# Schematic.net
KiCad netlist of a schematic drawn in EAGLE
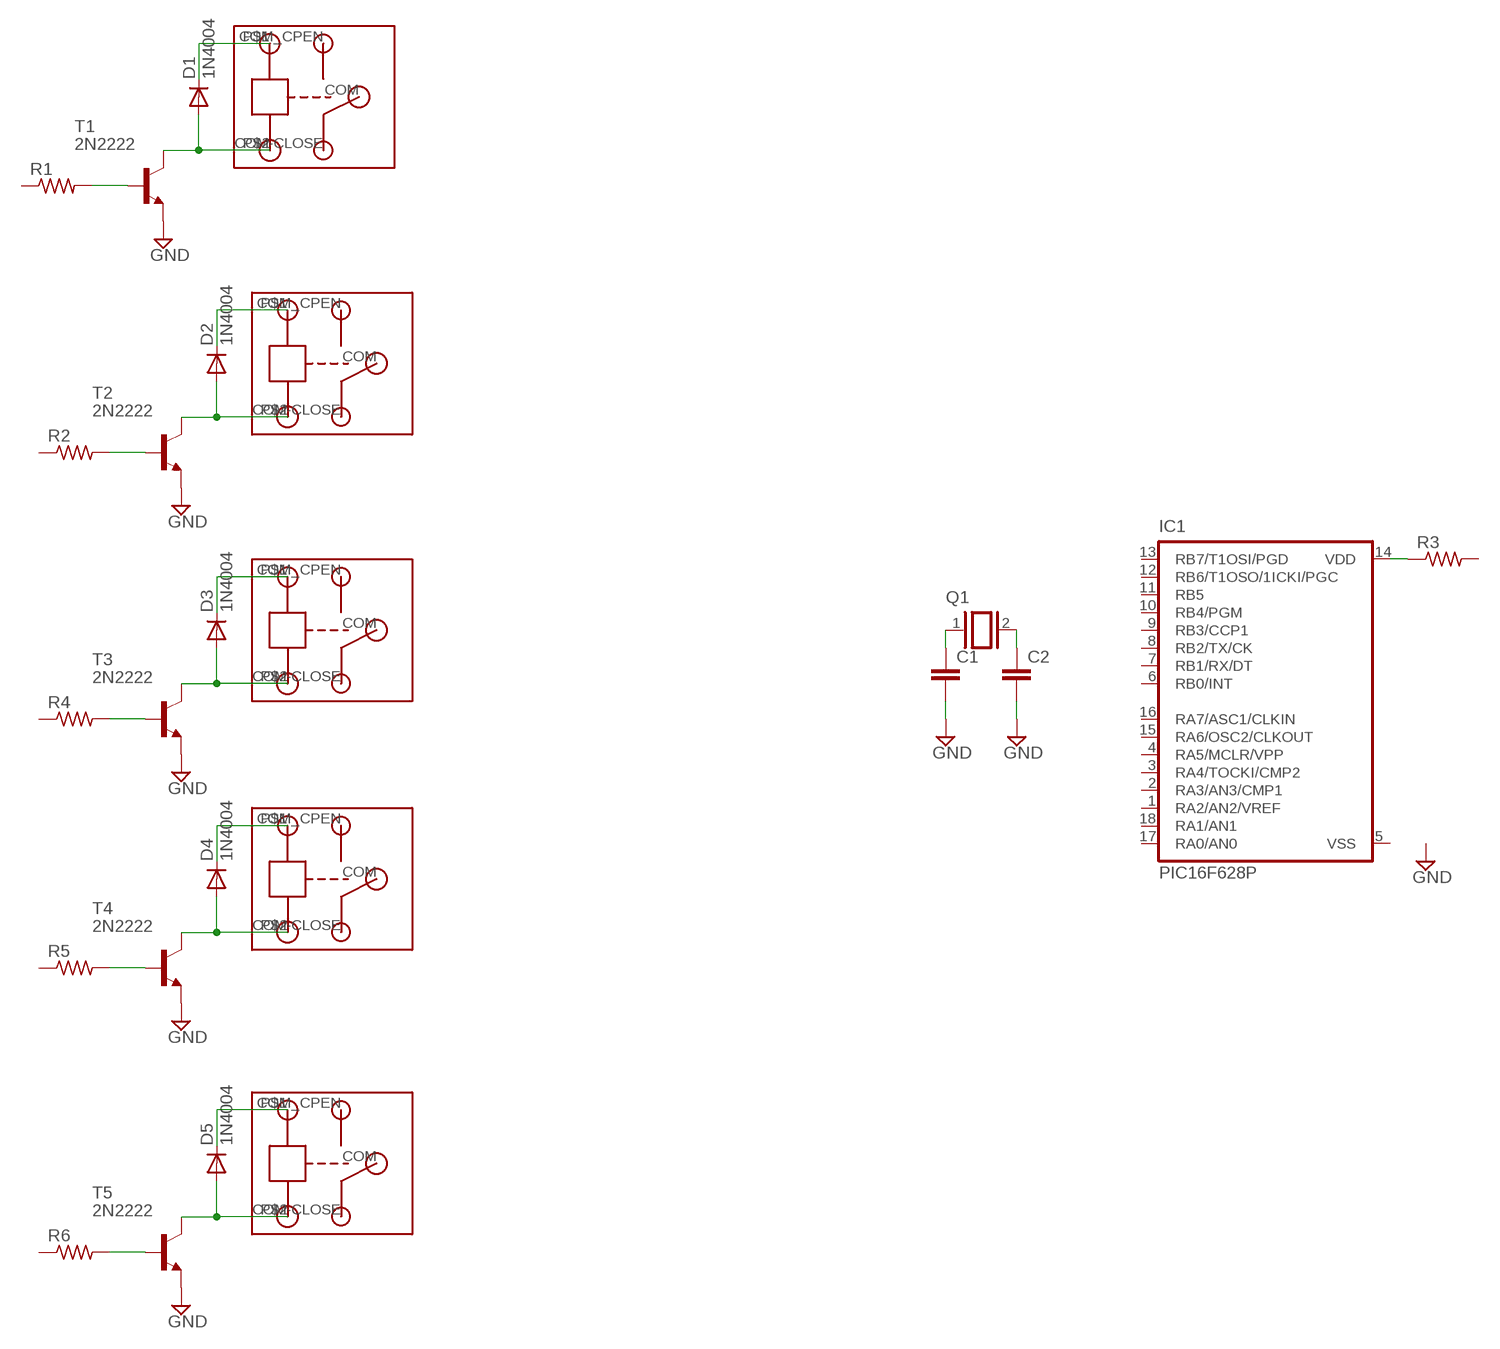
[diagram p0: schematic, sheet 1]

(export (version "E")
  (design (tool "Eeschema 10.0.6"))
  (components
    (comp (ref "C1")
      (value "C2,5-3")
      (footprint "eagle-import:C2.5-3")
      (libsource (lib "eagle-import") (part "C2,5-3"))
    )
    (comp (ref "C2")
      (value "C2,5-3")
      (footprint "eagle-import:C2.5-3")
      (libsource (lib "eagle-import") (part "C2,5-3"))
    )
    (comp (ref "D1")
      (value "1N4004")
      (footprint "eagle-import:DO41-10")
      (libsource (lib "eagle-import") (part "1N4004"))
    )
    (comp (ref "D2")
      (value "1N4004")
      (footprint "eagle-import:DO41-10")
      (libsource (lib "eagle-import") (part "1N4004"))
    )
    (comp (ref "D3")
      (value "1N4004")
      (footprint "eagle-import:DO41-10")
      (libsource (lib "eagle-import") (part "1N4004"))
    )
    (comp (ref "D4")
      (value "1N4004")
      (footprint "eagle-import:DO41-10")
      (libsource (lib "eagle-import") (part "1N4004"))
    )
    (comp (ref "D5")
      (value "1N4004")
      (footprint "eagle-import:DO41-10")
      (libsource (lib "eagle-import") (part "1N4004"))
    )
    (comp (ref "IC1")
      (value "PIC16F628P")
      (footprint "eagle-import:DIL18")
      (fields (field (name "MF") "MICROCHIP") (field (name "MPN") "PIC16F628-20/P"))
      (libsource (lib "eagle-import") (part "PIC16F628P"))
    )
    (comp (ref "Q1")
      (value "XTAL")
      (footprint "eagle-import:Q")
      (libsource (lib "eagle-import") (part "XTAL"))
    )
    (comp (ref "R1")
      (value "R-US_0207/7")
      (footprint "eagle-import:0207_7")
      (libsource (lib "eagle-import") (part "R-US_0207/7"))
    )
    (comp (ref "R2")
      (value "R-US_0207/7")
      (footprint "eagle-import:0207_7")
      (libsource (lib "eagle-import") (part "R-US_0207/7"))
    )
    (comp (ref "R3")
      (value "R-US_0207/12")
      (footprint "eagle-import:0207_12")
      (libsource (lib "eagle-import") (part "R-US_0207/12"))
    )
    (comp (ref "R4")
      (value "R-US_0207/7")
      (footprint "eagle-import:0207_7")
      (libsource (lib "eagle-import") (part "R-US_0207/7"))
    )
    (comp (ref "R5")
      (value "R-US_0207/7")
      (footprint "eagle-import:0207_7")
      (libsource (lib "eagle-import") (part "R-US_0207/7"))
    )
    (comp (ref "R6")
      (value "R-US_0207/7")
      (footprint "eagle-import:0207_7")
      (libsource (lib "eagle-import") (part "R-US_0207/7"))
    )
    (comp (ref "T1")
      (value "2N2222")
      (footprint "eagle-import:TO92-EBC-OVAL")
      (libsource (lib "eagle-import") (part "2N2222"))
    )
    (comp (ref "T2")
      (value "2N2222")
      (footprint "eagle-import:TO92-EBC-OVAL")
      (libsource (lib "eagle-import") (part "2N2222"))
    )
    (comp (ref "T3")
      (value "2N2222")
      (footprint "eagle-import:TO92-EBC-OVAL")
      (libsource (lib "eagle-import") (part "2N2222"))
    )
    (comp (ref "T4")
      (value "2N2222")
      (footprint "eagle-import:TO92-EBC-OVAL")
      (libsource (lib "eagle-import") (part "2N2222"))
    )
    (comp (ref "T5")
      (value "2N2222")
      (footprint "eagle-import:TO92-EBC-OVAL")
      (libsource (lib "eagle-import") (part "2N2222"))
    )
    (comp (ref "U$1")
      (value "RELAY")
      (footprint "eagle-import:RELAY")
      (libsource (lib "eagle-import") (part "RELAY"))
    )
    (comp (ref "U$2")
      (value "RELAY")
      (footprint "eagle-import:RELAY")
      (libsource (lib "eagle-import") (part "RELAY"))
    )
    (comp (ref "U$3")
      (value "RELAY")
      (footprint "eagle-import:RELAY")
      (libsource (lib "eagle-import") (part "RELAY"))
    )
    (comp (ref "U$4")
      (value "RELAY")
      (footprint "eagle-import:RELAY")
      (libsource (lib "eagle-import") (part "RELAY"))
    )
    (comp (ref "U$5")
      (value "RELAY")
      (footprint "eagle-import:RELAY")
      (libsource (lib "eagle-import") (part "RELAY"))
    )
  )
  (nets
    (net (code "1") (name "/VSS") (class "Default")
      (node (ref "IC1") (pin "5") (pinfunction "VSS_5") (pintype "power_in"))
    )
    (net (code "2") (name "GND") (class "Default")
      (node (ref "C1") (pin "2") (pinfunction "2_2") (pintype "passive"))
      (node (ref "C2") (pin "2") (pinfunction "2_2") (pintype "passive"))
      (node (ref "T1") (pin "E") (pinfunction "E_E") (pintype "passive"))
      (node (ref "T2") (pin "E") (pinfunction "E_E") (pintype "passive"))
      (node (ref "T3") (pin "E") (pinfunction "E_E") (pintype "passive"))
      (node (ref "T4") (pin "E") (pinfunction "E_E") (pintype "passive"))
      (node (ref "T5") (pin "E") (pinfunction "E_E") (pintype "passive"))
    )
    (net (code "3") (name "Net-(C1-Pad1)") (class "Default")
      (node (ref "C1") (pin "1") (pinfunction "1_1") (pintype "passive"))
      (node (ref "Q1") (pin "1") (pinfunction "1_1") (pintype "passive"))
    )
    (net (code "4") (name "Net-(C2-Pad1)") (class "Default")
      (node (ref "C2") (pin "1") (pinfunction "1_1") (pintype "passive"))
      (node (ref "Q1") (pin "2") (pinfunction "2_2") (pintype "passive"))
    )
    (net (code "5") (name "Net-(IC1-VDD)") (class "Default")
      (node (ref "IC1") (pin "14") (pinfunction "VDD_14") (pintype "power_in"))
      (node (ref "R3") (pin "1") (pinfunction "1_1") (pintype "passive"))
    )
    (net (code "6") (name "Net-(R1-Pad2)") (class "Default")
      (node (ref "R1") (pin "2") (pinfunction "2_2") (pintype "passive"))
      (node (ref "T1") (pin "B") (pinfunction "B_B") (pintype "passive"))
    )
    (net (code "7") (name "Net-(R2-Pad2)") (class "Default")
      (node (ref "R2") (pin "2") (pinfunction "2_2") (pintype "passive"))
      (node (ref "T2") (pin "B") (pinfunction "B_B") (pintype "passive"))
    )
    (net (code "8") (name "Net-(R4-Pad2)") (class "Default")
      (node (ref "R4") (pin "2") (pinfunction "2_2") (pintype "passive"))
      (node (ref "T3") (pin "B") (pinfunction "B_B") (pintype "passive"))
    )
    (net (code "9") (name "Net-(R5-Pad2)") (class "Default")
      (node (ref "R5") (pin "2") (pinfunction "2_2") (pintype "passive"))
      (node (ref "T4") (pin "B") (pinfunction "B_B") (pintype "passive"))
    )
    (net (code "10") (name "Net-(R6-Pad2)") (class "Default")
      (node (ref "R6") (pin "2") (pinfunction "2_2") (pintype "passive"))
      (node (ref "T5") (pin "B") (pinfunction "B_B") (pintype "passive"))
    )
    (net (code "11") (name "Net-(U$1-GND)") (class "Default")
      (node (ref "D1") (pin "A") (pinfunction "A_A") (pintype "passive"))
      (node (ref "T1") (pin "C") (pinfunction "C_C") (pintype "passive"))
      (node (ref "U$1") (pin "P$2") (pinfunction "GND_P$2") (pintype "bidirectional"))
    )
    (net (code "12") (name "Net-(U$1-IN)") (class "Default")
      (node (ref "D1") (pin "C") (pinfunction "C_C") (pintype "passive"))
      (node (ref "U$1") (pin "P$1") (pinfunction "IN_P$1") (pintype "bidirectional"))
    )
    (net (code "13") (name "Net-(U$2-GND)") (class "Default")
      (node (ref "D2") (pin "A") (pinfunction "A_A") (pintype "passive"))
      (node (ref "T2") (pin "C") (pinfunction "C_C") (pintype "passive"))
      (node (ref "U$2") (pin "P$2") (pinfunction "GND_P$2") (pintype "bidirectional"))
    )
    (net (code "14") (name "Net-(U$2-IN)") (class "Default")
      (node (ref "D2") (pin "C") (pinfunction "C_C") (pintype "passive"))
      (node (ref "U$2") (pin "P$1") (pinfunction "IN_P$1") (pintype "bidirectional"))
    )
    (net (code "15") (name "Net-(U$3-GND)") (class "Default")
      (node (ref "D3") (pin "A") (pinfunction "A_A") (pintype "passive"))
      (node (ref "T3") (pin "C") (pinfunction "C_C") (pintype "passive"))
      (node (ref "U$3") (pin "P$2") (pinfunction "GND_P$2") (pintype "bidirectional"))
    )
    (net (code "16") (name "Net-(U$3-IN)") (class "Default")
      (node (ref "D3") (pin "C") (pinfunction "C_C") (pintype "passive"))
      (node (ref "U$3") (pin "P$1") (pinfunction "IN_P$1") (pintype "bidirectional"))
    )
    (net (code "17") (name "Net-(U$4-GND)") (class "Default")
      (node (ref "D4") (pin "A") (pinfunction "A_A") (pintype "passive"))
      (node (ref "T4") (pin "C") (pinfunction "C_C") (pintype "passive"))
      (node (ref "U$4") (pin "P$2") (pinfunction "GND_P$2") (pintype "bidirectional"))
    )
    (net (code "18") (name "Net-(U$4-IN)") (class "Default")
      (node (ref "D4") (pin "C") (pinfunction "C_C") (pintype "passive"))
      (node (ref "U$4") (pin "P$1") (pinfunction "IN_P$1") (pintype "bidirectional"))
    )
    (net (code "19") (name "Net-(U$5-GND)") (class "Default")
      (node (ref "D5") (pin "A") (pinfunction "A_A") (pintype "passive"))
      (node (ref "T5") (pin "C") (pinfunction "C_C") (pintype "passive"))
      (node (ref "U$5") (pin "P$2") (pinfunction "GND_P$2") (pintype "bidirectional"))
    )
    (net (code "20") (name "Net-(U$5-IN)") (class "Default")
      (node (ref "D5") (pin "C") (pinfunction "C_C") (pintype "passive"))
      (node (ref "U$5") (pin "P$1") (pinfunction "IN_P$1") (pintype "bidirectional"))
    )
    (net (code "21") (name "unconnected-(IC1-RA0{slash}AN0-Pad17)") (class "Default")
      (node (ref "IC1") (pin "17") (pinfunction "RA0/AN0_17") (pintype "bidirectional"))
    )
    (net (code "22") (name "unconnected-(IC1-RA1{slash}AN1-Pad18)") (class "Default")
      (node (ref "IC1") (pin "18") (pinfunction "RA1/AN1_18") (pintype "bidirectional"))
    )
    (net (code "23") (name "unconnected-(IC1-RA2{slash}AN2{slash}VREF-Pad1)") (class "Default")
      (node (ref "IC1") (pin "1") (pinfunction "RA2/AN2/VREF_1") (pintype "bidirectional"))
    )
    (net (code "24") (name "unconnected-(IC1-RA3{slash}AN3{slash}CMP1-Pad2)") (class "Default")
      (node (ref "IC1") (pin "2") (pinfunction "RA3/AN3/CMP1_2") (pintype "bidirectional"))
    )
    (net (code "25") (name "unconnected-(IC1-RA4{slash}TOCKI{slash}CMP2-Pad3)") (class "Default")
      (node (ref "IC1") (pin "3") (pinfunction "RA4/TOCKI/CMP2_3") (pintype "bidirectional"))
    )
    (net (code "26") (name "unconnected-(IC1-RA5{slash}MCLR{slash}VPP-Pad4)") (class "Default")
      (node (ref "IC1") (pin "4") (pinfunction "RA5/MCLR/VPP_4") (pintype "input"))
    )
    (net (code "27") (name "unconnected-(IC1-RA6{slash}OSC2{slash}CLKOUT-Pad15)") (class "Default")
      (node (ref "IC1") (pin "15") (pinfunction "RA6/OSC2/CLKOUT_15") (pintype "bidirectional"))
    )
    (net (code "28") (name "unconnected-(IC1-RA7{slash}ASC1{slash}CLKIN-Pad16)") (class "Default")
      (node (ref "IC1") (pin "16") (pinfunction "RA7/ASC1/CLKIN_16") (pintype "bidirectional"))
    )
    (net (code "29") (name "unconnected-(IC1-RB0{slash}INT-Pad6)") (class "Default")
      (node (ref "IC1") (pin "6") (pinfunction "RB0/INT_6") (pintype "bidirectional"))
    )
    (net (code "30") (name "unconnected-(IC1-RB1{slash}RX{slash}DT-Pad7)") (class "Default")
      (node (ref "IC1") (pin "7") (pinfunction "RB1/RX/DT_7") (pintype "bidirectional"))
    )
    (net (code "31") (name "unconnected-(IC1-RB2{slash}TX{slash}CK-Pad8)") (class "Default")
      (node (ref "IC1") (pin "8") (pinfunction "RB2/TX/CK_8") (pintype "bidirectional"))
    )
    (net (code "32") (name "unconnected-(IC1-RB3{slash}CCP1-Pad9)") (class "Default")
      (node (ref "IC1") (pin "9") (pinfunction "RB3/CCP1_9") (pintype "bidirectional"))
    )
    (net (code "33") (name "unconnected-(IC1-RB4{slash}PGM-Pad10)") (class "Default")
      (node (ref "IC1") (pin "10") (pinfunction "RB4/PGM_10") (pintype "bidirectional"))
    )
    (net (code "34") (name "unconnected-(IC1-RB5-Pad11)") (class "Default")
      (node (ref "IC1") (pin "11") (pinfunction "RB5_11") (pintype "bidirectional"))
    )
    (net (code "35") (name "unconnected-(IC1-RB6{slash}T1OSO{slash}1ICKI{slash}PGC-Pad12)") (class "Default")
      (node (ref "IC1") (pin "12") (pinfunction "RB6/T1OSO/1ICKI/PGC_12") (pintype "bidirectional"))
    )
    (net (code "36") (name "unconnected-(IC1-RB7{slash}T1OSI{slash}PGD-Pad13)") (class "Default")
      (node (ref "IC1") (pin "13") (pinfunction "RB7/T1OSI/PGD_13") (pintype "bidirectional"))
    )
    (net (code "37") (name "unconnected-(R1-Pad1)") (class "Default")
      (node (ref "R1") (pin "1") (pinfunction "1_1") (pintype "passive"))
    )
    (net (code "38") (name "unconnected-(R2-Pad1)") (class "Default")
      (node (ref "R2") (pin "1") (pinfunction "1_1") (pintype "passive"))
    )
    (net (code "39") (name "unconnected-(R3-Pad2)") (class "Default")
      (node (ref "R3") (pin "2") (pinfunction "2_2") (pintype "passive"))
    )
    (net (code "40") (name "unconnected-(R4-Pad1)") (class "Default")
      (node (ref "R4") (pin "1") (pinfunction "1_1") (pintype "passive"))
    )
    (net (code "41") (name "unconnected-(R5-Pad1)") (class "Default")
      (node (ref "R5") (pin "1") (pinfunction "1_1") (pintype "passive"))
    )
    (net (code "42") (name "unconnected-(R6-Pad1)") (class "Default")
      (node (ref "R6") (pin "1") (pinfunction "1_1") (pintype "passive"))
    )
    (net (code "43") (name "unconnected-(U$1-COM-OPEN-PadCOM_CPEN)") (class "Default")
      (node (ref "U$1") (pin "COM_CPEN") (pinfunction "COM-OPEN_COM_CPEN") (pintype "bidirectional"))
    )
    (net (code "44") (name "unconnected-(U$1-PadCOM)") (class "Default")
      (node (ref "U$1") (pin "COM") (pinfunction "COM_COM") (pintype "bidirectional"))
    )
    (net (code "45") (name "unconnected-(U$1-PadCOM-CLOSE)") (class "Default")
      (node (ref "U$1") (pin "COM-CLOSE") (pinfunction "COM-CLOSE_COM-CLOSE") (pintype "bidirectional"))
    )
    (net (code "46") (name "unconnected-(U$2-COM-OPEN-PadCOM_CPEN)") (class "Default")
      (node (ref "U$2") (pin "COM_CPEN") (pinfunction "COM-OPEN_COM_CPEN") (pintype "bidirectional"))
    )
    (net (code "47") (name "unconnected-(U$2-PadCOM)") (class "Default")
      (node (ref "U$2") (pin "COM") (pinfunction "COM_COM") (pintype "bidirectional"))
    )
    (net (code "48") (name "unconnected-(U$2-PadCOM-CLOSE)") (class "Default")
      (node (ref "U$2") (pin "COM-CLOSE") (pinfunction "COM-CLOSE_COM-CLOSE") (pintype "bidirectional"))
    )
    (net (code "49") (name "unconnected-(U$3-COM-OPEN-PadCOM_CPEN)") (class "Default")
      (node (ref "U$3") (pin "COM_CPEN") (pinfunction "COM-OPEN_COM_CPEN") (pintype "bidirectional"))
    )
    (net (code "50") (name "unconnected-(U$3-PadCOM)") (class "Default")
      (node (ref "U$3") (pin "COM") (pinfunction "COM_COM") (pintype "bidirectional"))
    )
    (net (code "51") (name "unconnected-(U$3-PadCOM-CLOSE)") (class "Default")
      (node (ref "U$3") (pin "COM-CLOSE") (pinfunction "COM-CLOSE_COM-CLOSE") (pintype "bidirectional"))
    )
    (net (code "52") (name "unconnected-(U$4-COM-OPEN-PadCOM_CPEN)") (class "Default")
      (node (ref "U$4") (pin "COM_CPEN") (pinfunction "COM-OPEN_COM_CPEN") (pintype "bidirectional"))
    )
    (net (code "53") (name "unconnected-(U$4-PadCOM)") (class "Default")
      (node (ref "U$4") (pin "COM") (pinfunction "COM_COM") (pintype "bidirectional"))
    )
    (net (code "54") (name "unconnected-(U$4-PadCOM-CLOSE)") (class "Default")
      (node (ref "U$4") (pin "COM-CLOSE") (pinfunction "COM-CLOSE_COM-CLOSE") (pintype "bidirectional"))
    )
    (net (code "55") (name "unconnected-(U$5-COM-OPEN-PadCOM_CPEN)") (class "Default")
      (node (ref "U$5") (pin "COM_CPEN") (pinfunction "COM-OPEN_COM_CPEN") (pintype "bidirectional"))
    )
    (net (code "56") (name "unconnected-(U$5-PadCOM)") (class "Default")
      (node (ref "U$5") (pin "COM") (pinfunction "COM_COM") (pintype "bidirectional"))
    )
    (net (code "57") (name "unconnected-(U$5-PadCOM-CLOSE)") (class "Default")
      (node (ref "U$5") (pin "COM-CLOSE") (pinfunction "COM-CLOSE_COM-CLOSE") (pintype "bidirectional"))
    )
  )
)
